# Nav_Ducer_IO.net
KiCad netlist of a schematic drawn in Altium Designer
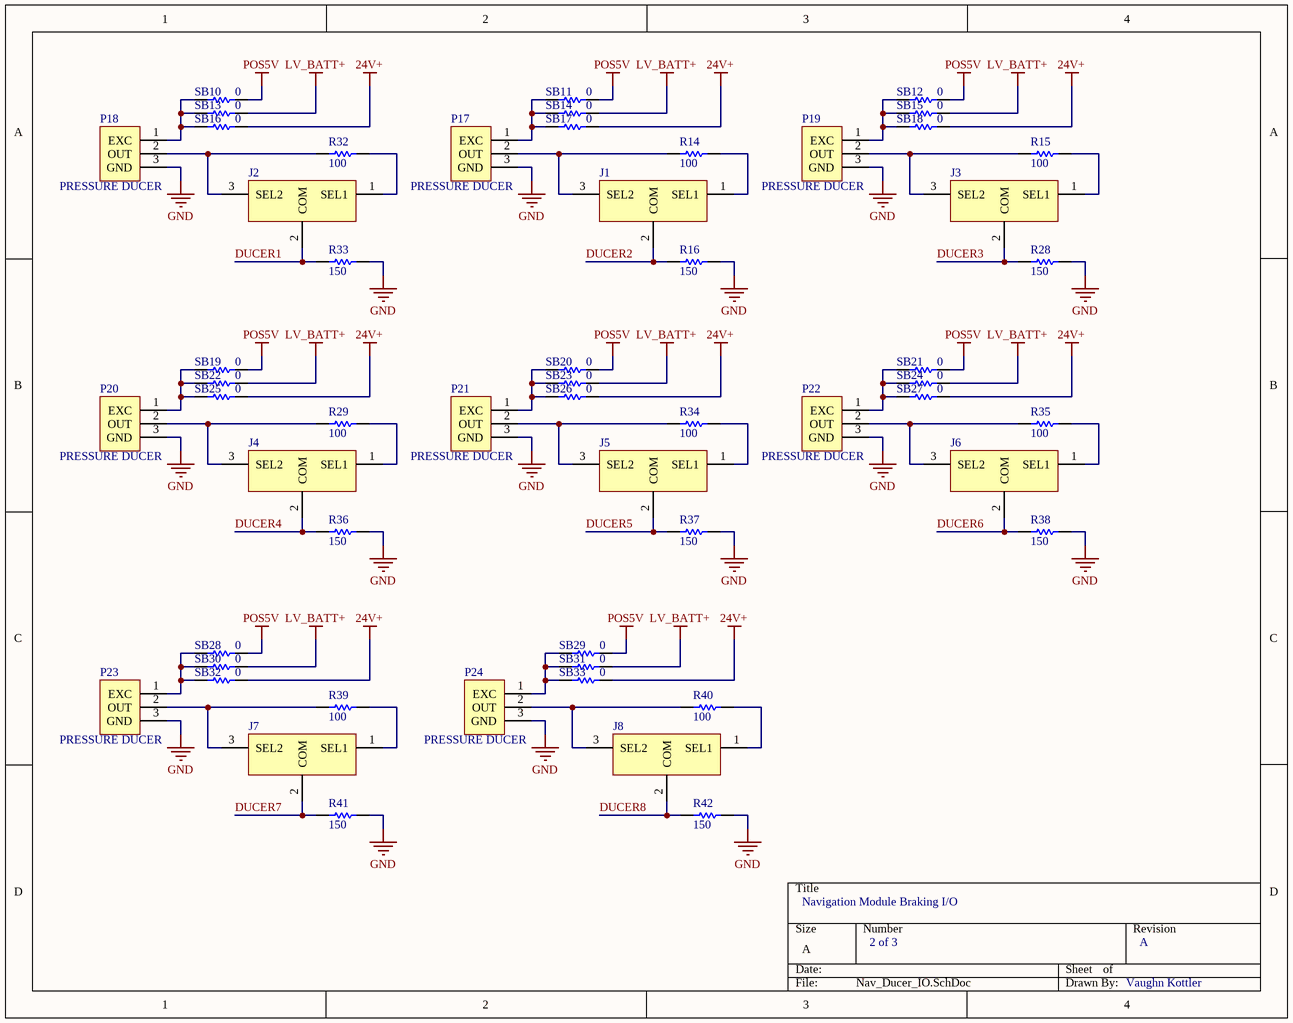
[diagram p0: Nav_Ducer_IO.SchDoc]

(export (version "E")
  (design (tool "Eeschema 10.0.6"))
  (components
    (comp (ref "J1") (value "SINGLE_SEL") (footprint "SEL") (libsource (lib "connector") (part "SINGLE_SEL")))
    (comp (ref "J2") (value "SINGLE_SEL") (footprint "SEL") (libsource (lib "connector") (part "SINGLE_SEL")))
    (comp (ref "J3") (value "SINGLE_SEL") (footprint "SEL") (libsource (lib "connector") (part "SINGLE_SEL")))
    (comp (ref "J4") (value "SINGLE_SEL") (footprint "SEL") (libsource (lib "connector") (part "SINGLE_SEL")))
    (comp (ref "J5") (value "SINGLE_SEL") (footprint "SEL") (libsource (lib "connector") (part "SINGLE_SEL")))
    (comp (ref "J6") (value "SINGLE_SEL") (footprint "SEL") (libsource (lib "connector") (part "SINGLE_SEL")))
    (comp (ref "J7") (value "SINGLE_SEL") (footprint "SEL") (libsource (lib "connector") (part "SINGLE_SEL")))
    (comp (ref "J8") (value "SINGLE_SEL") (footprint "SEL") (libsource (lib "connector") (part "SINGLE_SEL")))
    (comp (ref "P17")
      (value "PRESSURE DUCER")
      (footprint "3POS TERM BLOCK")
      (libsource (lib "connector") (part "PRESSURE DUCER"))
    )
    (comp (ref "P18")
      (value "PRESSURE DUCER")
      (footprint "3POS TERM BLOCK")
      (libsource (lib "connector") (part "PRESSURE DUCER"))
    )
    (comp (ref "P19")
      (value "PRESSURE DUCER")
      (footprint "3POS TERM BLOCK")
      (libsource (lib "connector") (part "PRESSURE DUCER"))
    )
    (comp (ref "P20")
      (value "PRESSURE DUCER")
      (footprint "3POS TERM BLOCK")
      (libsource (lib "connector") (part "PRESSURE DUCER"))
    )
    (comp (ref "P21")
      (value "PRESSURE DUCER")
      (footprint "3POS TERM BLOCK")
      (libsource (lib "connector") (part "PRESSURE DUCER"))
    )
    (comp (ref "P22")
      (value "PRESSURE DUCER")
      (footprint "3POS TERM BLOCK")
      (libsource (lib "connector") (part "PRESSURE DUCER"))
    )
    (comp (ref "P23")
      (value "PRESSURE DUCER")
      (footprint "3POS TERM BLOCK")
      (libsource (lib "connector") (part "PRESSURE DUCER"))
    )
    (comp (ref "P24")
      (value "PRESSURE DUCER")
      (footprint "3POS TERM BLOCK")
      (libsource (lib "connector") (part "PRESSURE DUCER"))
    )
    (comp (ref "R14")
      (value "100")
      (footprint "6-0805_M")
      (description "Resistor")
      (fields (field (name "Comment") "Res1") (field (name "PUBLISHER") "Altium Limited"))
      (libsource (lib "Miscellaneous Devices") (part "Res1"))
    )
    (comp (ref "R15")
      (value "100")
      (footprint "6-0805_M")
      (description "Resistor")
      (fields (field (name "Comment") "Res1") (field (name "PUBLISHER") "Altium Limited"))
      (libsource (lib "Miscellaneous Devices") (part "Res1"))
    )
    (comp (ref "R16")
      (value "150")
      (footprint "6-0805_M")
      (description "Resistor")
      (fields (field (name "Comment") "Res1") (field (name "PUBLISHER") "Altium Limited"))
      (libsource (lib "Miscellaneous Devices") (part "Res1"))
    )
    (comp (ref "R28")
      (value "150")
      (footprint "6-0805_M")
      (description "Resistor")
      (fields (field (name "Comment") "Res1") (field (name "PUBLISHER") "Altium Limited"))
      (libsource (lib "Miscellaneous Devices") (part "Res1"))
    )
    (comp (ref "R29")
      (value "100")
      (footprint "6-0805_M")
      (description "Resistor")
      (fields (field (name "Comment") "Res1") (field (name "PUBLISHER") "Altium Limited"))
      (libsource (lib "Miscellaneous Devices") (part "Res1"))
    )
    (comp (ref "R32")
      (value "100")
      (footprint "6-0805_M")
      (description "Resistor")
      (fields (field (name "Comment") "Res1") (field (name "PUBLISHER") "Altium Limited"))
      (libsource (lib "Miscellaneous Devices") (part "Res1"))
    )
    (comp (ref "R33")
      (value "150")
      (footprint "6-0805_M")
      (description "Resistor")
      (fields (field (name "Comment") "Res1") (field (name "PUBLISHER") "Altium Limited"))
      (libsource (lib "Miscellaneous Devices") (part "Res1"))
    )
    (comp (ref "R34")
      (value "100")
      (footprint "6-0805_M")
      (description "Resistor")
      (fields (field (name "Comment") "Res1") (field (name "PUBLISHER") "Altium Limited"))
      (libsource (lib "Miscellaneous Devices") (part "Res1"))
    )
    (comp (ref "R35")
      (value "100")
      (footprint "6-0805_M")
      (description "Resistor")
      (fields (field (name "Comment") "Res1") (field (name "PUBLISHER") "Altium Limited"))
      (libsource (lib "Miscellaneous Devices") (part "Res1"))
    )
    (comp (ref "R36")
      (value "150")
      (footprint "6-0805_M")
      (description "Resistor")
      (fields (field (name "Comment") "Res1") (field (name "PUBLISHER") "Altium Limited"))
      (libsource (lib "Miscellaneous Devices") (part "Res1"))
    )
    (comp (ref "R37")
      (value "150")
      (footprint "6-0805_M")
      (description "Resistor")
      (fields (field (name "Comment") "Res1") (field (name "PUBLISHER") "Altium Limited"))
      (libsource (lib "Miscellaneous Devices") (part "Res1"))
    )
    (comp (ref "R38")
      (value "150")
      (footprint "6-0805_M")
      (description "Resistor")
      (fields (field (name "Comment") "Res1") (field (name "PUBLISHER") "Altium Limited"))
      (libsource (lib "Miscellaneous Devices") (part "Res1"))
    )
    (comp (ref "R39")
      (value "100")
      (footprint "6-0805_M")
      (description "Resistor")
      (fields (field (name "Comment") "Res1") (field (name "PUBLISHER") "Altium Limited"))
      (libsource (lib "Miscellaneous Devices") (part "Res1"))
    )
    (comp (ref "R40")
      (value "100")
      (footprint "6-0805_M")
      (description "Resistor")
      (fields (field (name "Comment") "Res1") (field (name "PUBLISHER") "Altium Limited"))
      (libsource (lib "Miscellaneous Devices") (part "Res1"))
    )
    (comp (ref "R41")
      (value "150")
      (footprint "6-0805_M")
      (description "Resistor")
      (fields (field (name "Comment") "Res1") (field (name "PUBLISHER") "Altium Limited"))
      (libsource (lib "Miscellaneous Devices") (part "Res1"))
    )
    (comp (ref "R42")
      (value "150")
      (footprint "6-0805_M")
      (description "Resistor")
      (fields (field (name "Comment") "Res1") (field (name "PUBLISHER") "Altium Limited"))
      (libsource (lib "Miscellaneous Devices") (part "Res1"))
    )
    (comp (ref "SB10")
      (value "0")
      (footprint "6-0805_M")
      (description "Resistor")
      (fields (field (name "Comment") "Res1") (field (name "PUBLISHER") "Altium Limited"))
      (libsource (lib "Miscellaneous Devices") (part "Res1"))
    )
    (comp (ref "SB11")
      (value "0")
      (footprint "6-0805_M")
      (description "Resistor")
      (fields (field (name "Comment") "Res1") (field (name "PUBLISHER") "Altium Limited"))
      (libsource (lib "Miscellaneous Devices") (part "Res1"))
    )
    (comp (ref "SB12")
      (value "0")
      (footprint "6-0805_M")
      (description "Resistor")
      (fields (field (name "Comment") "Res1") (field (name "PUBLISHER") "Altium Limited"))
      (libsource (lib "Miscellaneous Devices") (part "Res1"))
    )
    (comp (ref "SB13")
      (value "0")
      (footprint "6-0805_M")
      (description "Resistor")
      (fields (field (name "Comment") "Res1") (field (name "PUBLISHER") "Altium Limited"))
      (libsource (lib "Miscellaneous Devices") (part "Res1"))
    )
    (comp (ref "SB14")
      (value "0")
      (footprint "6-0805_M")
      (description "Resistor")
      (fields (field (name "Comment") "Res1") (field (name "PUBLISHER") "Altium Limited"))
      (libsource (lib "Miscellaneous Devices") (part "Res1"))
    )
    (comp (ref "SB15")
      (value "0")
      (footprint "6-0805_M")
      (description "Resistor")
      (fields (field (name "Comment") "Res1") (field (name "PUBLISHER") "Altium Limited"))
      (libsource (lib "Miscellaneous Devices") (part "Res1"))
    )
    (comp (ref "SB16")
      (value "0")
      (footprint "6-0805_M")
      (description "Resistor")
      (fields (field (name "Comment") "Res1") (field (name "PUBLISHER") "Altium Limited"))
      (libsource (lib "Miscellaneous Devices") (part "Res1"))
    )
    (comp (ref "SB17")
      (value "0")
      (footprint "6-0805_M")
      (description "Resistor")
      (fields (field (name "Comment") "Res1") (field (name "PUBLISHER") "Altium Limited"))
      (libsource (lib "Miscellaneous Devices") (part "Res1"))
    )
    (comp (ref "SB18")
      (value "0")
      (footprint "6-0805_M")
      (description "Resistor")
      (fields (field (name "Comment") "Res1") (field (name "PUBLISHER") "Altium Limited"))
      (libsource (lib "Miscellaneous Devices") (part "Res1"))
    )
    (comp (ref "SB19")
      (value "0")
      (footprint "6-0805_M")
      (description "Resistor")
      (fields (field (name "Comment") "Res1") (field (name "PUBLISHER") "Altium Limited"))
      (libsource (lib "Miscellaneous Devices") (part "Res1"))
    )
    (comp (ref "SB20")
      (value "0")
      (footprint "6-0805_M")
      (description "Resistor")
      (fields (field (name "Comment") "Res1") (field (name "PUBLISHER") "Altium Limited"))
      (libsource (lib "Miscellaneous Devices") (part "Res1"))
    )
    (comp (ref "SB21")
      (value "0")
      (footprint "6-0805_M")
      (description "Resistor")
      (fields (field (name "Comment") "Res1") (field (name "PUBLISHER") "Altium Limited"))
      (libsource (lib "Miscellaneous Devices") (part "Res1"))
    )
    (comp (ref "SB22")
      (value "0")
      (footprint "6-0805_M")
      (description "Resistor")
      (fields (field (name "Comment") "Res1") (field (name "PUBLISHER") "Altium Limited"))
      (libsource (lib "Miscellaneous Devices") (part "Res1"))
    )
    (comp (ref "SB23")
      (value "0")
      (footprint "6-0805_M")
      (description "Resistor")
      (fields (field (name "Comment") "Res1") (field (name "PUBLISHER") "Altium Limited"))
      (libsource (lib "Miscellaneous Devices") (part "Res1"))
    )
    (comp (ref "SB24")
      (value "0")
      (footprint "6-0805_M")
      (description "Resistor")
      (fields (field (name "Comment") "Res1") (field (name "PUBLISHER") "Altium Limited"))
      (libsource (lib "Miscellaneous Devices") (part "Res1"))
    )
    (comp (ref "SB25")
      (value "0")
      (footprint "6-0805_M")
      (description "Resistor")
      (fields (field (name "Comment") "Res1") (field (name "PUBLISHER") "Altium Limited"))
      (libsource (lib "Miscellaneous Devices") (part "Res1"))
    )
    (comp (ref "SB26")
      (value "0")
      (footprint "6-0805_M")
      (description "Resistor")
      (fields (field (name "Comment") "Res1") (field (name "PUBLISHER") "Altium Limited"))
      (libsource (lib "Miscellaneous Devices") (part "Res1"))
    )
    (comp (ref "SB27")
      (value "0")
      (footprint "6-0805_M")
      (description "Resistor")
      (fields (field (name "Comment") "Res1") (field (name "PUBLISHER") "Altium Limited"))
      (libsource (lib "Miscellaneous Devices") (part "Res1"))
    )
    (comp (ref "SB28")
      (value "0")
      (footprint "6-0805_M")
      (description "Resistor")
      (fields (field (name "Comment") "Res1") (field (name "PUBLISHER") "Altium Limited"))
      (libsource (lib "Miscellaneous Devices") (part "Res1"))
    )
    (comp (ref "SB29")
      (value "0")
      (footprint "6-0805_M")
      (description "Resistor")
      (fields (field (name "Comment") "Res1") (field (name "PUBLISHER") "Altium Limited"))
      (libsource (lib "Miscellaneous Devices") (part "Res1"))
    )
    (comp (ref "SB30")
      (value "0")
      (footprint "6-0805_M")
      (description "Resistor")
      (fields (field (name "Comment") "Res1") (field (name "PUBLISHER") "Altium Limited"))
      (libsource (lib "Miscellaneous Devices") (part "Res1"))
    )
    (comp (ref "SB31")
      (value "0")
      (footprint "6-0805_M")
      (description "Resistor")
      (fields (field (name "Comment") "Res1") (field (name "PUBLISHER") "Altium Limited"))
      (libsource (lib "Miscellaneous Devices") (part "Res1"))
    )
    (comp (ref "SB32")
      (value "0")
      (footprint "6-0805_M")
      (description "Resistor")
      (fields (field (name "Comment") "Res1") (field (name "PUBLISHER") "Altium Limited"))
      (libsource (lib "Miscellaneous Devices") (part "Res1"))
    )
    (comp (ref "SB33")
      (value "0")
      (footprint "6-0805_M")
      (description "Resistor")
      (fields (field (name "Comment") "Res1") (field (name "PUBLISHER") "Altium Limited"))
      (libsource (lib "Miscellaneous Devices") (part "Res1"))
    )
  )
  (nets
    (net (code "1") (name "/DUCER1") (class "Default")
      (node (ref "J2") (pin "2") (pinfunction "COM_2") (pintype "passive"))
      (node (ref "R33") (pin "2") (pinfunction "2_2") (pintype "passive"))
    )
    (net (code "2") (name "/DUCER2") (class "Default")
      (node (ref "J1") (pin "2") (pinfunction "COM_2") (pintype "passive"))
      (node (ref "R16") (pin "2") (pinfunction "2_2") (pintype "passive"))
    )
    (net (code "3") (name "/DUCER3") (class "Default")
      (node (ref "J3") (pin "2") (pinfunction "COM_2") (pintype "passive"))
      (node (ref "R28") (pin "2") (pinfunction "2_2") (pintype "passive"))
    )
    (net (code "4") (name "/DUCER4") (class "Default")
      (node (ref "J4") (pin "2") (pinfunction "COM_2") (pintype "passive"))
      (node (ref "R36") (pin "2") (pinfunction "2_2") (pintype "passive"))
    )
    (net (code "5") (name "/DUCER5") (class "Default")
      (node (ref "J5") (pin "2") (pinfunction "COM_2") (pintype "passive"))
      (node (ref "R37") (pin "2") (pinfunction "2_2") (pintype "passive"))
    )
    (net (code "6") (name "/DUCER6") (class "Default")
      (node (ref "J6") (pin "2") (pinfunction "COM_2") (pintype "passive"))
      (node (ref "R38") (pin "2") (pinfunction "2_2") (pintype "passive"))
    )
    (net (code "7") (name "/DUCER7") (class "Default")
      (node (ref "J7") (pin "2") (pinfunction "COM_2") (pintype "passive"))
      (node (ref "R41") (pin "2") (pinfunction "2_2") (pintype "passive"))
    )
    (net (code "8") (name "/DUCER8") (class "Default")
      (node (ref "J8") (pin "2") (pinfunction "COM_2") (pintype "passive"))
      (node (ref "R42") (pin "2") (pinfunction "2_2") (pintype "passive"))
    )
    (net (code "9") (name "24V+") (class "Default")
      (node (ref "SB16") (pin "1") (pinfunction "1_1") (pintype "passive"))
      (node (ref "SB17") (pin "1") (pinfunction "1_1") (pintype "passive"))
      (node (ref "SB18") (pin "1") (pinfunction "1_1") (pintype "passive"))
      (node (ref "SB25") (pin "1") (pinfunction "1_1") (pintype "passive"))
      (node (ref "SB26") (pin "1") (pinfunction "1_1") (pintype "passive"))
      (node (ref "SB27") (pin "1") (pinfunction "1_1") (pintype "passive"))
      (node (ref "SB32") (pin "1") (pinfunction "1_1") (pintype "passive"))
      (node (ref "SB33") (pin "1") (pinfunction "1_1") (pintype "passive"))
    )
    (net (code "10") (name "GND") (class "Default")
      (node (ref "P17") (pin "3") (pinfunction "GND_3") (pintype "passive"))
      (node (ref "P18") (pin "3") (pinfunction "GND_3") (pintype "passive"))
      (node (ref "P19") (pin "3") (pinfunction "GND_3") (pintype "passive"))
      (node (ref "P20") (pin "3") (pinfunction "GND_3") (pintype "passive"))
      (node (ref "P21") (pin "3") (pinfunction "GND_3") (pintype "passive"))
      (node (ref "P22") (pin "3") (pinfunction "GND_3") (pintype "passive"))
      (node (ref "P23") (pin "3") (pinfunction "GND_3") (pintype "passive"))
      (node (ref "P24") (pin "3") (pinfunction "GND_3") (pintype "passive"))
      (node (ref "R16") (pin "1") (pinfunction "1_1") (pintype "passive"))
      (node (ref "R28") (pin "1") (pinfunction "1_1") (pintype "passive"))
      (node (ref "R33") (pin "1") (pinfunction "1_1") (pintype "passive"))
      (node (ref "R36") (pin "1") (pinfunction "1_1") (pintype "passive"))
      (node (ref "R37") (pin "1") (pinfunction "1_1") (pintype "passive"))
      (node (ref "R38") (pin "1") (pinfunction "1_1") (pintype "passive"))
      (node (ref "R41") (pin "1") (pinfunction "1_1") (pintype "passive"))
      (node (ref "R42") (pin "1") (pinfunction "1_1") (pintype "passive"))
    )
    (net (code "11") (name "LV_BATT+") (class "Default")
      (node (ref "SB13") (pin "1") (pinfunction "1_1") (pintype "passive"))
      (node (ref "SB14") (pin "1") (pinfunction "1_1") (pintype "passive"))
      (node (ref "SB15") (pin "1") (pinfunction "1_1") (pintype "passive"))
      (node (ref "SB22") (pin "1") (pinfunction "1_1") (pintype "passive"))
      (node (ref "SB23") (pin "1") (pinfunction "1_1") (pintype "passive"))
      (node (ref "SB24") (pin "1") (pinfunction "1_1") (pintype "passive"))
      (node (ref "SB30") (pin "1") (pinfunction "1_1") (pintype "passive"))
      (node (ref "SB31") (pin "1") (pinfunction "1_1") (pintype "passive"))
    )
    (net (code "12") (name "Net-(J1-SEL1)") (class "Default")
      (node (ref "J1") (pin "1") (pinfunction "SEL1_1") (pintype "passive"))
      (node (ref "R14") (pin "1") (pinfunction "1_1") (pintype "passive"))
    )
    (net (code "13") (name "Net-(J1-SEL2)") (class "Default")
      (node (ref "J1") (pin "3") (pinfunction "SEL2_3") (pintype "passive"))
      (node (ref "P17") (pin "2") (pinfunction "OUT_2") (pintype "passive"))
      (node (ref "R14") (pin "2") (pinfunction "2_2") (pintype "passive"))
    )
    (net (code "14") (name "Net-(J2-SEL1)") (class "Default")
      (node (ref "J2") (pin "1") (pinfunction "SEL1_1") (pintype "passive"))
      (node (ref "R32") (pin "1") (pinfunction "1_1") (pintype "passive"))
    )
    (net (code "15") (name "Net-(J2-SEL2)") (class "Default")
      (node (ref "J2") (pin "3") (pinfunction "SEL2_3") (pintype "passive"))
      (node (ref "P18") (pin "2") (pinfunction "OUT_2") (pintype "passive"))
      (node (ref "R32") (pin "2") (pinfunction "2_2") (pintype "passive"))
    )
    (net (code "16") (name "Net-(J3-SEL1)") (class "Default")
      (node (ref "J3") (pin "1") (pinfunction "SEL1_1") (pintype "passive"))
      (node (ref "R15") (pin "1") (pinfunction "1_1") (pintype "passive"))
    )
    (net (code "17") (name "Net-(J3-SEL2)") (class "Default")
      (node (ref "J3") (pin "3") (pinfunction "SEL2_3") (pintype "passive"))
      (node (ref "P19") (pin "2") (pinfunction "OUT_2") (pintype "passive"))
      (node (ref "R15") (pin "2") (pinfunction "2_2") (pintype "passive"))
    )
    (net (code "18") (name "Net-(J4-SEL1)") (class "Default")
      (node (ref "J4") (pin "1") (pinfunction "SEL1_1") (pintype "passive"))
      (node (ref "R29") (pin "1") (pinfunction "1_1") (pintype "passive"))
    )
    (net (code "19") (name "Net-(J4-SEL2)") (class "Default")
      (node (ref "J4") (pin "3") (pinfunction "SEL2_3") (pintype "passive"))
      (node (ref "P20") (pin "2") (pinfunction "OUT_2") (pintype "passive"))
      (node (ref "R29") (pin "2") (pinfunction "2_2") (pintype "passive"))
    )
    (net (code "20") (name "Net-(J5-SEL1)") (class "Default")
      (node (ref "J5") (pin "1") (pinfunction "SEL1_1") (pintype "passive"))
      (node (ref "R34") (pin "1") (pinfunction "1_1") (pintype "passive"))
    )
    (net (code "21") (name "Net-(J5-SEL2)") (class "Default")
      (node (ref "J5") (pin "3") (pinfunction "SEL2_3") (pintype "passive"))
      (node (ref "P21") (pin "2") (pinfunction "OUT_2") (pintype "passive"))
      (node (ref "R34") (pin "2") (pinfunction "2_2") (pintype "passive"))
    )
    (net (code "22") (name "Net-(J6-SEL1)") (class "Default")
      (node (ref "J6") (pin "1") (pinfunction "SEL1_1") (pintype "passive"))
      (node (ref "R35") (pin "1") (pinfunction "1_1") (pintype "passive"))
    )
    (net (code "23") (name "Net-(J6-SEL2)") (class "Default")
      (node (ref "J6") (pin "3") (pinfunction "SEL2_3") (pintype "passive"))
      (node (ref "P22") (pin "2") (pinfunction "OUT_2") (pintype "passive"))
      (node (ref "R35") (pin "2") (pinfunction "2_2") (pintype "passive"))
    )
    (net (code "24") (name "Net-(J7-SEL1)") (class "Default")
      (node (ref "J7") (pin "1") (pinfunction "SEL1_1") (pintype "passive"))
      (node (ref "R39") (pin "1") (pinfunction "1_1") (pintype "passive"))
    )
    (net (code "25") (name "Net-(J7-SEL2)") (class "Default")
      (node (ref "J7") (pin "3") (pinfunction "SEL2_3") (pintype "passive"))
      (node (ref "P23") (pin "2") (pinfunction "OUT_2") (pintype "passive"))
      (node (ref "R39") (pin "2") (pinfunction "2_2") (pintype "passive"))
    )
    (net (code "26") (name "Net-(J8-SEL1)") (class "Default")
      (node (ref "J8") (pin "1") (pinfunction "SEL1_1") (pintype "passive"))
      (node (ref "R40") (pin "1") (pinfunction "1_1") (pintype "passive"))
    )
    (net (code "27") (name "Net-(J8-SEL2)") (class "Default")
      (node (ref "J8") (pin "3") (pinfunction "SEL2_3") (pintype "passive"))
      (node (ref "P24") (pin "2") (pinfunction "OUT_2") (pintype "passive"))
      (node (ref "R40") (pin "2") (pinfunction "2_2") (pintype "passive"))
    )
    (net (code "28") (name "Net-(P17-EXC)") (class "Default")
      (node (ref "P17") (pin "1") (pinfunction "EXC_1") (pintype "passive"))
      (node (ref "SB11") (pin "2") (pinfunction "2_2") (pintype "passive"))
      (node (ref "SB14") (pin "2") (pinfunction "2_2") (pintype "passive"))
      (node (ref "SB17") (pin "2") (pinfunction "2_2") (pintype "passive"))
    )
    (net (code "29") (name "Net-(P18-EXC)") (class "Default")
      (node (ref "P18") (pin "1") (pinfunction "EXC_1") (pintype "passive"))
      (node (ref "SB10") (pin "2") (pinfunction "2_2") (pintype "passive"))
      (node (ref "SB13") (pin "2") (pinfunction "2_2") (pintype "passive"))
      (node (ref "SB16") (pin "2") (pinfunction "2_2") (pintype "passive"))
    )
    (net (code "30") (name "Net-(P19-EXC)") (class "Default")
      (node (ref "P19") (pin "1") (pinfunction "EXC_1") (pintype "passive"))
      (node (ref "SB12") (pin "2") (pinfunction "2_2") (pintype "passive"))
      (node (ref "SB15") (pin "2") (pinfunction "2_2") (pintype "passive"))
      (node (ref "SB18") (pin "2") (pinfunction "2_2") (pintype "passive"))
    )
    (net (code "31") (name "Net-(P20-EXC)") (class "Default")
      (node (ref "P20") (pin "1") (pinfunction "EXC_1") (pintype "passive"))
      (node (ref "SB19") (pin "2") (pinfunction "2_2") (pintype "passive"))
      (node (ref "SB22") (pin "2") (pinfunction "2_2") (pintype "passive"))
      (node (ref "SB25") (pin "2") (pinfunction "2_2") (pintype "passive"))
    )
    (net (code "32") (name "Net-(P21-EXC)") (class "Default")
      (node (ref "P21") (pin "1") (pinfunction "EXC_1") (pintype "passive"))
      (node (ref "SB20") (pin "2") (pinfunction "2_2") (pintype "passive"))
      (node (ref "SB23") (pin "2") (pinfunction "2_2") (pintype "passive"))
      (node (ref "SB26") (pin "2") (pinfunction "2_2") (pintype "passive"))
    )
    (net (code "33") (name "Net-(P22-EXC)") (class "Default")
      (node (ref "P22") (pin "1") (pinfunction "EXC_1") (pintype "passive"))
      (node (ref "SB21") (pin "2") (pinfunction "2_2") (pintype "passive"))
      (node (ref "SB24") (pin "2") (pinfunction "2_2") (pintype "passive"))
      (node (ref "SB27") (pin "2") (pinfunction "2_2") (pintype "passive"))
    )
    (net (code "34") (name "Net-(P23-EXC)") (class "Default")
      (node (ref "P23") (pin "1") (pinfunction "EXC_1") (pintype "passive"))
      (node (ref "SB28") (pin "2") (pinfunction "2_2") (pintype "passive"))
      (node (ref "SB30") (pin "2") (pinfunction "2_2") (pintype "passive"))
      (node (ref "SB32") (pin "2") (pinfunction "2_2") (pintype "passive"))
    )
    (net (code "35") (name "Net-(P24-EXC)") (class "Default")
      (node (ref "P24") (pin "1") (pinfunction "EXC_1") (pintype "passive"))
      (node (ref "SB29") (pin "2") (pinfunction "2_2") (pintype "passive"))
      (node (ref "SB31") (pin "2") (pinfunction "2_2") (pintype "passive"))
      (node (ref "SB33") (pin "2") (pinfunction "2_2") (pintype "passive"))
    )
    (net (code "36") (name "POS5V") (class "Default")
      (node (ref "SB10") (pin "1") (pinfunction "1_1") (pintype "passive"))
      (node (ref "SB11") (pin "1") (pinfunction "1_1") (pintype "passive"))
      (node (ref "SB12") (pin "1") (pinfunction "1_1") (pintype "passive"))
      (node (ref "SB19") (pin "1") (pinfunction "1_1") (pintype "passive"))
      (node (ref "SB20") (pin "1") (pinfunction "1_1") (pintype "passive"))
      (node (ref "SB21") (pin "1") (pinfunction "1_1") (pintype "passive"))
      (node (ref "SB28") (pin "1") (pinfunction "1_1") (pintype "passive"))
      (node (ref "SB29") (pin "1") (pinfunction "1_1") (pintype "passive"))
    )
  )
)
